# GateControl.net
KiCad netlist of a schematic drawn in EAGLE
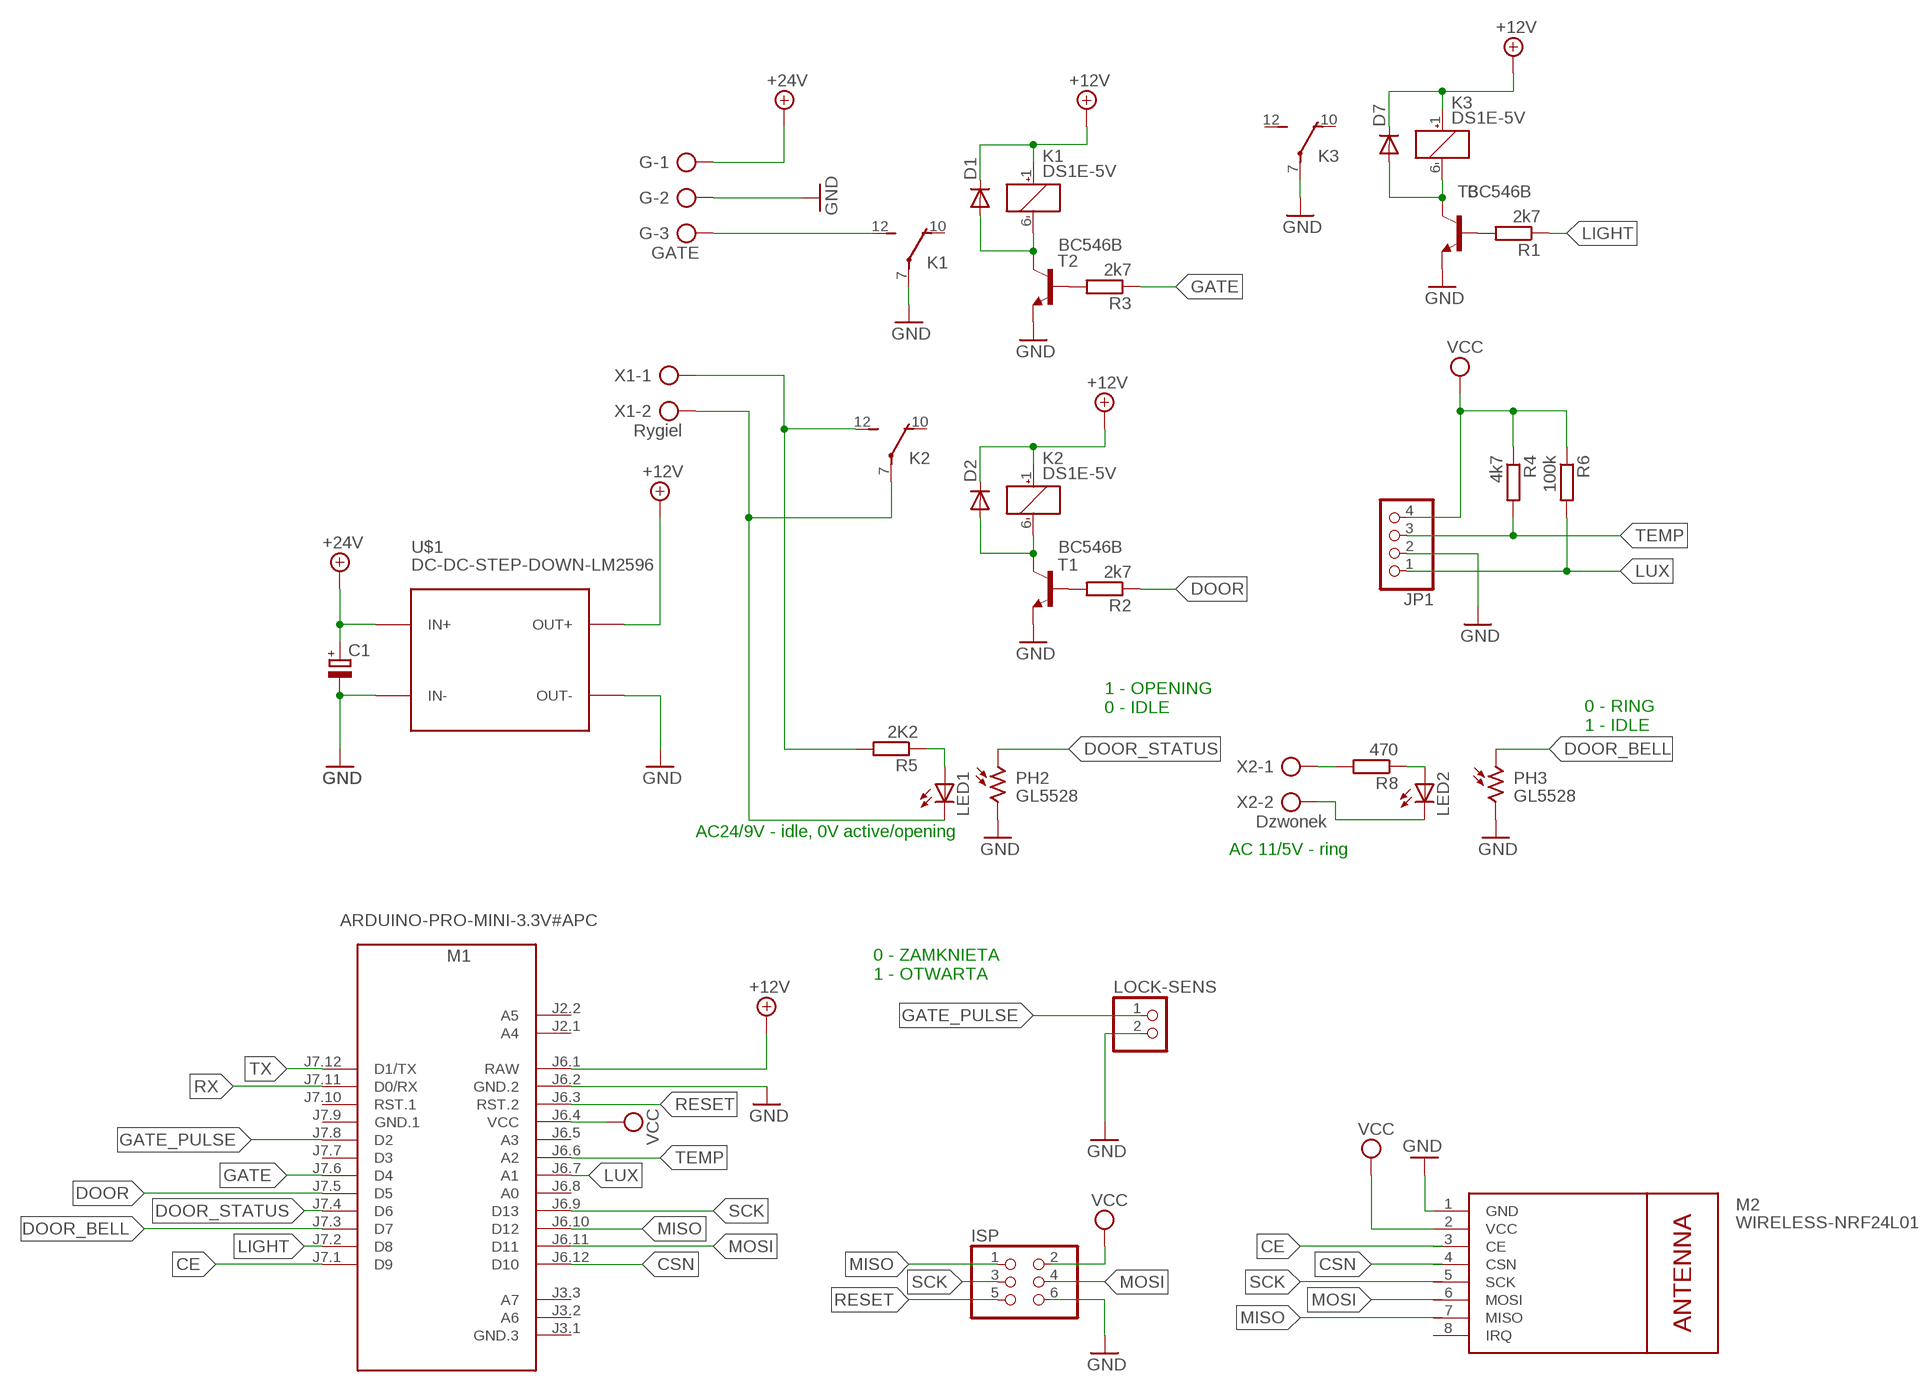
[diagram p0: schematic, sheet 1]

(export (version "E")
  (design (tool "Eeschema 10.0.6"))
  (components
    (comp (ref "C1")
      (value "CPOL-EUE3.5-10")
      (footprint "eagle-import:E3,5-10")
      (libsource (lib "eagle-import") (part "CPOL-EUE3.5-10"))
    )
    (comp (ref "D1")
      (value "DIODE-C1702-05")
      (footprint "eagle-import:C1702-05")
      (libsource (lib "eagle-import") (part "DIODE-C1702-05"))
    )
    (comp (ref "D2")
      (value "DIODE-C1702-05")
      (footprint "eagle-import:C1702-05")
      (libsource (lib "eagle-import") (part "DIODE-C1702-05"))
    )
    (comp (ref "D7")
      (value "DIODE-C1702-05")
      (footprint "eagle-import:C1702-05")
      (libsource (lib "eagle-import") (part "DIODE-C1702-05"))
    )
    (comp (ref "G")
      (value "GATE")
      (footprint "eagle-import:AK500_3")
      (libsource (lib "eagle-import") (part "AK500/3"))
    )
    (comp (ref "ISP")
      (value "PINHD-2X03_2.54")
      (footprint "eagle-import:2X03")
      (libsource (lib "eagle-import") (part "PINHD-2X03_2.54"))
    )
    (comp (ref "JP1")
      (value "PINHD-1X04_2.54")
      (footprint "eagle-import:1X04")
      (libsource (lib "eagle-import") (part "PINHD-1X04_2.54"))
    )
    (comp (ref "K1")
      (value "DS1E-5V")
      (footprint "eagle-import:DS1E")
      (libsource (lib "eagle-import") (part "DS1E-?5V"))
    )
    (comp (ref "K2")
      (value "DS1E-5V")
      (footprint "eagle-import:DS1E")
      (libsource (lib "eagle-import") (part "DS1E-?5V"))
    )
    (comp (ref "K3")
      (value "DS1E-5V")
      (footprint "eagle-import:DS1E")
      (libsource (lib "eagle-import") (part "DS1E-?5V"))
    )
    (comp (ref "LED1")
      (value "LED5MM")
      (footprint "eagle-import:LED5MM")
      (libsource (lib "eagle-import") (part "LED5MM"))
    )
    (comp (ref "LED2")
      (value "LED5MM")
      (footprint "eagle-import:LED5MM")
      (libsource (lib "eagle-import") (part "LED5MM"))
    )
    (comp (ref "LOCK-SENS")
      (value "PINHD-1X02_2.54")
      (footprint "eagle-import:1X02")
      (libsource (lib "eagle-import") (part "PINHD-1X02_2.54"))
    )
    (comp (ref "M1")
      (value "ARDUINO-PRO-MINI-3.3V#APC")
      (footprint "eagle-import:ARDUINO-PRO-MINI#APC")
      (libsource (lib "eagle-import") (part "ARDUINO-PRO-MINI-#APC3.3V"))
    )
    (comp (ref "M2")
      (value "WIRELESS-NRF24L01")
      (footprint "eagle-import:WIRELESS-NRF24L01")
      (libsource (lib "eagle-import") (part "WIRELESS-NRF24L01"))
    )
    (comp (ref "PH2")
      (value "GL5528")
      (footprint "eagle-import:TO46-VT200")
      (libsource (lib "eagle-import") (part "VT20N1"))
    )
    (comp (ref "PH3")
      (value "GL5528")
      (footprint "eagle-import:TO46-VT200")
      (libsource (lib "eagle-import") (part "VT20N1"))
    )
    (comp (ref "R1")
      (value "2k7")
      (footprint "eagle-import:0309V")
      (libsource (lib "eagle-import") (part "R-EU_0309/V"))
    )
    (comp (ref "R2")
      (value "2k7")
      (footprint "eagle-import:0309V")
      (libsource (lib "eagle-import") (part "R-EU_0309/V"))
    )
    (comp (ref "R3")
      (value "2k7")
      (footprint "eagle-import:0309V")
      (libsource (lib "eagle-import") (part "R-EU_0309/V"))
    )
    (comp (ref "R4")
      (value "4k7")
      (footprint "eagle-import:0309V")
      (libsource (lib "eagle-import") (part "R-EU_0309/V"))
    )
    (comp (ref "R5")
      (value "2K2")
      (footprint "eagle-import:0309V")
      (libsource (lib "eagle-import") (part "R-EU_0309/V"))
    )
    (comp (ref "R6")
      (value "100k")
      (footprint "eagle-import:0309V")
      (libsource (lib "eagle-import") (part "R-EU_0309/V"))
    )
    (comp (ref "R8")
      (value "470")
      (footprint "eagle-import:0309V")
      (libsource (lib "eagle-import") (part "R-EU_0309/V"))
    )
    (comp (ref "T1")
      (value "BC546B")
      (footprint "eagle-import:TO92-EBC")
      (libsource (lib "eagle-import") (part "BC546B"))
    )
    (comp (ref "T2")
      (value "BC546B")
      (footprint "eagle-import:TO92-EBC")
      (libsource (lib "eagle-import") (part "BC546B"))
    )
    (comp (ref "T3")
      (value "BC546B")
      (footprint "eagle-import:TO92-EBC")
      (libsource (lib "eagle-import") (part "BC546B"))
    )
    (comp (ref "U$1")
      (value "DC-DC-STEP-DOWN-LM2596")
      (footprint "eagle-import:DC-DC-STEP-DOWN-LM2596")
      (libsource (lib "eagle-import") (part "DC-DC-STEP-DOWN-LM2596"))
    )
    (comp (ref "X1")
      (value "Rygiel")
      (footprint "eagle-import:AK500_2")
      (libsource (lib "eagle-import") (part "AK500/2"))
    )
    (comp (ref "X2")
      (value "Dzwonek")
      (footprint "eagle-import:AK500_2")
      (libsource (lib "eagle-import") (part "AK500/2"))
    )
  )
  (nets
    (net (code "1") (name "+12V") (class "Default")
      (node (ref "D1") (pin "C") (pinfunction "C_C") (pintype "passive"))
      (node (ref "D2") (pin "C") (pinfunction "C_C") (pintype "passive"))
      (node (ref "D7") (pin "C") (pinfunction "C_C") (pintype "passive"))
      (node (ref "K1") (pin "1") (pinfunction "+_1") (pintype "passive"))
      (node (ref "K2") (pin "1") (pinfunction "+_1") (pintype "passive"))
      (node (ref "K3") (pin "1") (pinfunction "+_1") (pintype "passive"))
      (node (ref "M1") (pin "J6.1") (pinfunction "RAW_J6.1") (pintype "power_in"))
      (node (ref "U$1") (pin "OUT+") (pinfunction "OUT+_OUT+") (pintype "bidirectional"))
    )
    (net (code "2") (name "+24V") (class "Default")
      (node (ref "C1") (pin "+") (pinfunction "+_+") (pintype "passive"))
      (node (ref "G") (pin "1") (pinfunction "KL_1") (pintype "passive"))
      (node (ref "U$1") (pin "IN+") (pinfunction "IN+_IN+") (pintype "bidirectional"))
    )
    (net (code "3") (name "/GND.1") (class "Default")
      (node (ref "M1") (pin "J7.9") (pinfunction "GND.1_J7.9") (pintype "power_in"))
    )
    (net (code "4") (name "CE") (class "Default")
      (node (ref "M1") (pin "J7.1") (pinfunction "D9_J7.1") (pintype "bidirectional"))
      (node (ref "M2") (pin "3") (pinfunction "CE_3") (pintype "bidirectional"))
    )
    (net (code "5") (name "CSN") (class "Default")
      (node (ref "M1") (pin "J6.12") (pinfunction "D10_J6.12") (pintype "bidirectional"))
      (node (ref "M2") (pin "4") (pinfunction "CSN_4") (pintype "bidirectional"))
    )
    (net (code "6") (name "DOOR") (class "Default")
      (node (ref "M1") (pin "J7.5") (pinfunction "D5_J7.5") (pintype "bidirectional"))
      (node (ref "R2") (pin "1") (pinfunction "1_1") (pintype "passive"))
    )
    (net (code "7") (name "DOOR_BELL") (class "Default")
      (node (ref "M1") (pin "J7.3") (pinfunction "D7_J7.3") (pintype "bidirectional"))
      (node (ref "PH3") (pin "1") (pinfunction "1_1") (pintype "passive"))
    )
    (net (code "8") (name "DOOR_STATUS") (class "Default")
      (node (ref "M1") (pin "J7.4") (pinfunction "D6_J7.4") (pintype "bidirectional"))
      (node (ref "PH2") (pin "1") (pinfunction "1_1") (pintype "passive"))
    )
    (net (code "9") (name "GATE") (class "Default")
      (node (ref "M1") (pin "J7.6") (pinfunction "D4_J7.6") (pintype "bidirectional"))
      (node (ref "R3") (pin "1") (pinfunction "1_1") (pintype "passive"))
    )
    (net (code "10") (name "GATE_PULSE") (class "Default")
      (node (ref "LOCK-SENS") (pin "1") (pinfunction "1_1") (pintype "passive"))
      (node (ref "M1") (pin "J7.8") (pinfunction "D2_J7.8") (pintype "bidirectional"))
    )
    (net (code "11") (name "GND") (class "Default")
      (node (ref "C1") (pin "-") (pinfunction "-_-") (pintype "passive"))
      (node (ref "G") (pin "2") (pinfunction "KL_2") (pintype "passive"))
      (node (ref "ISP") (pin "6") (pinfunction "6_6") (pintype "passive"))
      (node (ref "JP1") (pin "2") (pinfunction "2_2") (pintype "passive"))
      (node (ref "K1") (pin "7") (pinfunction "P_7") (pintype "passive"))
      (node (ref "K3") (pin "7") (pinfunction "P_7") (pintype "passive"))
      (node (ref "LOCK-SENS") (pin "2") (pinfunction "2_2") (pintype "passive"))
      (node (ref "M1") (pin "J6.2") (pinfunction "GND.2_J6.2") (pintype "power_in"))
      (node (ref "M2") (pin "1") (pinfunction "GND_1") (pintype "power_in"))
      (node (ref "PH2") (pin "2") (pinfunction "2_2") (pintype "passive"))
      (node (ref "PH3") (pin "2") (pinfunction "2_2") (pintype "passive"))
      (node (ref "T1") (pin "E") (pinfunction "E_E") (pintype "passive"))
      (node (ref "T2") (pin "E") (pinfunction "E_E") (pintype "passive"))
      (node (ref "T3") (pin "E") (pinfunction "E_E") (pintype "passive"))
      (node (ref "U$1") (pin "IN-") (pinfunction "IN-_IN-") (pintype "bidirectional"))
      (node (ref "U$1") (pin "OUT-") (pinfunction "OUT-_OUT-") (pintype "bidirectional"))
    )
    (net (code "12") (name "LIGHT") (class "Default")
      (node (ref "M1") (pin "J7.2") (pinfunction "D8_J7.2") (pintype "bidirectional"))
      (node (ref "R1") (pin "1") (pinfunction "1_1") (pintype "passive"))
    )
    (net (code "13") (name "LUX") (class "Default")
      (node (ref "JP1") (pin "1") (pinfunction "1_1") (pintype "passive"))
      (node (ref "M1") (pin "J6.7") (pinfunction "A1_J6.7") (pintype "bidirectional"))
      (node (ref "R6") (pin "2") (pinfunction "2_2") (pintype "passive"))
    )
    (net (code "14") (name "MISO") (class "Default")
      (node (ref "ISP") (pin "1") (pinfunction "1_1") (pintype "passive"))
      (node (ref "M1") (pin "J6.10") (pinfunction "D12_J6.10") (pintype "bidirectional"))
      (node (ref "M2") (pin "7") (pinfunction "MISO_7") (pintype "bidirectional"))
    )
    (net (code "15") (name "MOSI") (class "Default")
      (node (ref "ISP") (pin "4") (pinfunction "4_4") (pintype "passive"))
      (node (ref "M1") (pin "J6.11") (pinfunction "D11_J6.11") (pintype "bidirectional"))
      (node (ref "M2") (pin "6") (pinfunction "MOSI_6") (pintype "bidirectional"))
    )
    (net (code "16") (name "Net-(GC-KL)") (class "Default")
      (node (ref "G") (pin "3") (pinfunction "KL_3") (pintype "passive"))
      (node (ref "K1") (pin "12") (pinfunction "S_12") (pintype "passive"))
    )
    (net (code "17") (name "Net-(K1A--)") (class "Default")
      (node (ref "D1") (pin "A") (pinfunction "A_A") (pintype "passive"))
      (node (ref "K1") (pin "6") (pinfunction "-_6") (pintype "passive"))
      (node (ref "T2") (pin "C") (pinfunction "C_C") (pintype "passive"))
    )
    (net (code "18") (name "Net-(K2A--)") (class "Default")
      (node (ref "D2") (pin "A") (pinfunction "A_A") (pintype "passive"))
      (node (ref "K2") (pin "6") (pinfunction "-_6") (pintype "passive"))
      (node (ref "T1") (pin "C") (pinfunction "C_C") (pintype "passive"))
    )
    (net (code "19") (name "Net-(K2B-P)") (class "Default")
      (node (ref "K2") (pin "7") (pinfunction "P_7") (pintype "passive"))
      (node (ref "LED1") (pin "K") (pinfunction "C_K") (pintype "passive"))
      (node (ref "X1") (pin "2") (pinfunction "KL_2") (pintype "passive"))
    )
    (net (code "20") (name "Net-(K2B-S)") (class "Default")
      (node (ref "K2") (pin "12") (pinfunction "S_12") (pintype "passive"))
      (node (ref "R5") (pin "2") (pinfunction "2_2") (pintype "passive"))
      (node (ref "X1") (pin "1") (pinfunction "KL_1") (pintype "passive"))
    )
    (net (code "21") (name "Net-(K3A--)") (class "Default")
      (node (ref "D7") (pin "A") (pinfunction "A_A") (pintype "passive"))
      (node (ref "K3") (pin "6") (pinfunction "-_6") (pintype "passive"))
      (node (ref "T3") (pin "C") (pinfunction "C_C") (pintype "passive"))
    )
    (net (code "22") (name "Net-(LED1-PadA)") (class "Default")
      (node (ref "LED1") (pin "A") (pinfunction "A_A") (pintype "passive"))
      (node (ref "R5") (pin "1") (pinfunction "1_1") (pintype "passive"))
    )
    (net (code "23") (name "Net-(LED2-C)") (class "Default")
      (node (ref "LED2") (pin "K") (pinfunction "C_K") (pintype "passive"))
      (node (ref "X2") (pin "2") (pinfunction "KL_2") (pintype "passive"))
    )
    (net (code "24") (name "Net-(LED2-PadA)") (class "Default")
      (node (ref "LED2") (pin "A") (pinfunction "A_A") (pintype "passive"))
      (node (ref "R8") (pin "1") (pinfunction "1_1") (pintype "passive"))
    )
    (net (code "25") (name "Net-(R1-Pad2)") (class "Default")
      (node (ref "R1") (pin "2") (pinfunction "2_2") (pintype "passive"))
      (node (ref "T3") (pin "B") (pinfunction "B_B") (pintype "passive"))
    )
    (net (code "26") (name "Net-(R2-Pad2)") (class "Default")
      (node (ref "R2") (pin "2") (pinfunction "2_2") (pintype "passive"))
      (node (ref "T1") (pin "B") (pinfunction "B_B") (pintype "passive"))
    )
    (net (code "27") (name "Net-(R3-Pad2)") (class "Default")
      (node (ref "R3") (pin "2") (pinfunction "2_2") (pintype "passive"))
      (node (ref "T2") (pin "B") (pinfunction "B_B") (pintype "passive"))
    )
    (net (code "28") (name "Net-(X2A-KL)") (class "Default")
      (node (ref "R8") (pin "2") (pinfunction "2_2") (pintype "passive"))
      (node (ref "X2") (pin "1") (pinfunction "KL_1") (pintype "passive"))
    )
    (net (code "29") (name "RESET") (class "Default")
      (node (ref "ISP") (pin "5") (pinfunction "5_5") (pintype "passive"))
      (node (ref "M1") (pin "J6.3") (pinfunction "RST.2_J6.3") (pintype "bidirectional"))
    )
    (net (code "30") (name "RX") (class "Default")
      (node (ref "M1") (pin "J7.11") (pinfunction "D0/RX_J7.11") (pintype "bidirectional"))
    )
    (net (code "31") (name "SCK") (class "Default")
      (node (ref "ISP") (pin "3") (pinfunction "3_3") (pintype "passive"))
      (node (ref "M1") (pin "J6.9") (pinfunction "D13_J6.9") (pintype "bidirectional"))
      (node (ref "M2") (pin "5") (pinfunction "SCK_5") (pintype "bidirectional"))
    )
    (net (code "32") (name "TEMP") (class "Default")
      (node (ref "JP1") (pin "3") (pinfunction "3_3") (pintype "passive"))
      (node (ref "M1") (pin "J6.6") (pinfunction "A2_J6.6") (pintype "bidirectional"))
      (node (ref "R4") (pin "2") (pinfunction "2_2") (pintype "passive"))
    )
    (net (code "33") (name "TX") (class "Default")
      (node (ref "M1") (pin "J7.12") (pinfunction "D1/TX_J7.12") (pintype "bidirectional"))
    )
    (net (code "34") (name "VCC") (class "Default")
      (node (ref "ISP") (pin "2") (pinfunction "2_2") (pintype "passive"))
      (node (ref "JP1") (pin "4") (pinfunction "4_4") (pintype "passive"))
      (node (ref "M1") (pin "J6.4") (pinfunction "VCC_J6.4") (pintype "power_in"))
      (node (ref "M2") (pin "2") (pinfunction "VCC_2") (pintype "power_in"))
      (node (ref "R4") (pin "1") (pinfunction "1_1") (pintype "passive"))
      (node (ref "R6") (pin "1") (pinfunction "1_1") (pintype "passive"))
    )
    (net (code "35") (name "unconnected-(K1B-O-Pad10)") (class "Default")
      (node (ref "K1") (pin "10") (pinfunction "O_10") (pintype "passive"))
    )
    (net (code "36") (name "unconnected-(K2B-O-Pad10)") (class "Default")
      (node (ref "K2") (pin "10") (pinfunction "O_10") (pintype "passive"))
    )
    (net (code "37") (name "unconnected-(K3B-O-Pad10)") (class "Default")
      (node (ref "K3") (pin "10") (pinfunction "O_10") (pintype "passive"))
    )
    (net (code "38") (name "unconnected-(K3B-S-Pad12)") (class "Default")
      (node (ref "K3") (pin "12") (pinfunction "S_12") (pintype "passive"))
    )
    (net (code "39") (name "unconnected-(M1-A0-PadJ6.8)") (class "Default")
      (node (ref "M1") (pin "J6.8") (pinfunction "A0_J6.8") (pintype "bidirectional"))
    )
    (net (code "40") (name "unconnected-(M1-A3-PadJ6.5)") (class "Default")
      (node (ref "M1") (pin "J6.5") (pinfunction "A3_J6.5") (pintype "bidirectional"))
    )
    (net (code "41") (name "unconnected-(M1-A4-PadJ2.1)") (class "Default")
      (node (ref "M1") (pin "J2.1") (pinfunction "A4_J2.1") (pintype "bidirectional"))
    )
    (net (code "42") (name "unconnected-(M1-A5-PadJ2.2)") (class "Default")
      (node (ref "M1") (pin "J2.2") (pinfunction "A5_J2.2") (pintype "bidirectional"))
    )
    (net (code "43") (name "unconnected-(M1-A6-PadJ3.2)") (class "Default")
      (node (ref "M1") (pin "J3.2") (pinfunction "A6_J3.2") (pintype "bidirectional"))
    )
    (net (code "44") (name "unconnected-(M1-A7-PadJ3.3)") (class "Default")
      (node (ref "M1") (pin "J3.3") (pinfunction "A7_J3.3") (pintype "bidirectional"))
    )
    (net (code "45") (name "unconnected-(M1-D3-PadJ7.7)") (class "Default")
      (node (ref "M1") (pin "J7.7") (pinfunction "D3_J7.7") (pintype "bidirectional"))
    )
    (net (code "46") (name "unconnected-(M1-GND.3-PadJ3.1)") (class "Default")
      (node (ref "M1") (pin "J3.1") (pinfunction "GND.3_J3.1") (pintype "bidirectional"))
    )
    (net (code "47") (name "unconnected-(M1-RST.1-PadJ7.10)") (class "Default")
      (node (ref "M1") (pin "J7.10") (pinfunction "RST.1_J7.10") (pintype "bidirectional"))
    )
    (net (code "48") (name "unconnected-(M2-IRQ-Pad8)") (class "Default")
      (node (ref "M2") (pin "8") (pinfunction "IRQ_8") (pintype "bidirectional"))
    )
  )
)
